# schematic.net
KiCad netlist of a schematic drawn in EAGLE
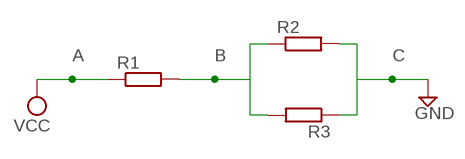
[diagram p0: schematic, sheet 1]

(export (version "E")
  (design (tool "Eeschema 10.0.6"))
  (components
    (comp (ref "R1")
      (value "R-EU_0207/10")
      (footprint "eagle-import:0207_10")
      (libsource (lib "eagle-import") (part "R-EU_0207/10"))
    )
    (comp (ref "R2")
      (value "R-EU_0207/10")
      (footprint "eagle-import:0207_10")
      (libsource (lib "eagle-import") (part "R-EU_0207/10"))
    )
    (comp (ref "R3")
      (value "R-EU_0207/10")
      (footprint "eagle-import:0207_10")
      (libsource (lib "eagle-import") (part "R-EU_0207/10"))
    )
  )
  (nets
    (net (code "1") (name "/B") (class "Default")
      (node (ref "R1") (pin "2") (pinfunction "2_2") (pintype "passive"))
      (node (ref "R2") (pin "1") (pinfunction "1_1") (pintype "passive"))
      (node (ref "R3") (pin "2") (pinfunction "2_2") (pintype "passive"))
    )
    (net (code "2") (name "GND") (class "Default")
      (node (ref "R2") (pin "2") (pinfunction "2_2") (pintype "passive"))
      (node (ref "R3") (pin "1") (pinfunction "1_1") (pintype "passive"))
    )
    (net (code "3") (name "VCC") (class "Default")
      (node (ref "R1") (pin "1") (pinfunction "1_1") (pintype "passive"))
    )
  )
)
